# 02_MCU.net
KiCad netlist of a schematic drawn in Altium Designer
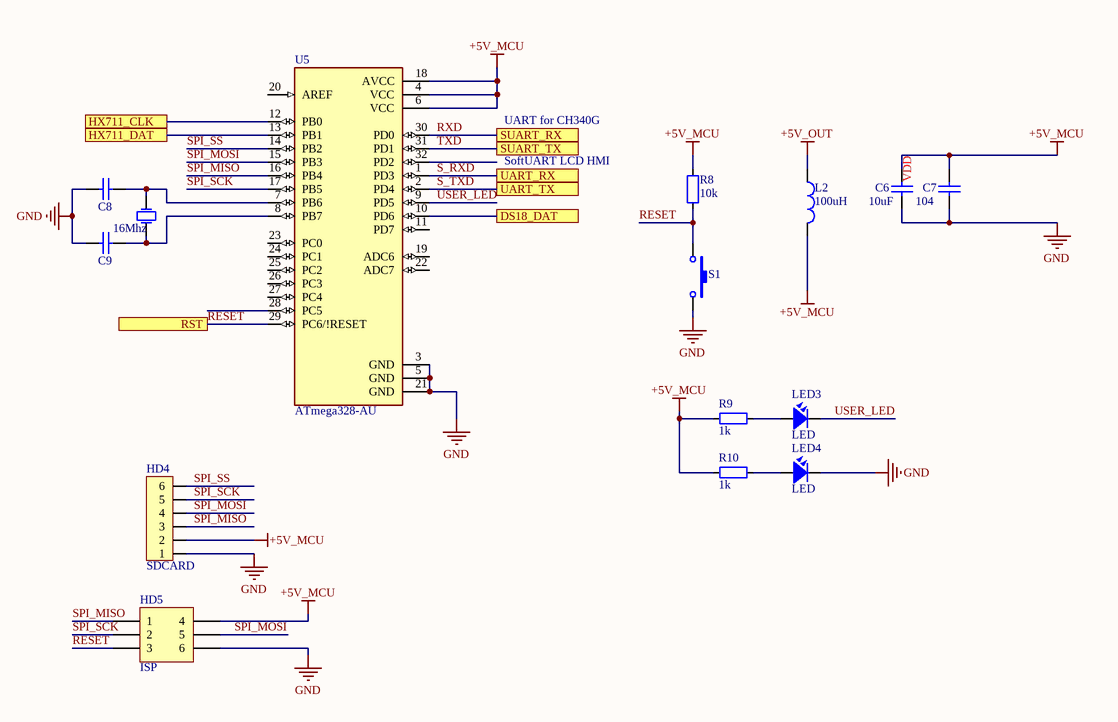
[diagram p0: [02] MCU.SchDoc]

(export (version "E")
  (design (tool "Eeschema 10.0.6"))
  (components
    (comp (ref "C6")
      (value "10uF")
      (footprint "CAP_0805")
      (description "Capacitor")
      (fields (field (name "PUBLISHER") "Altium Limited"))
      (libsource (lib "My Library") (part "CapSMD"))
    )
    (comp (ref "C7")
      (value "104")
      (footprint "CAP_0805")
      (description "Capacitor")
      (fields (field (name "PUBLISHER") "Altium Limited"))
      (libsource (lib "My Library") (part "CapSMD"))
    )
    (comp (ref "C8")
      (value "Capacitor Ceramic")
      (footprint "CAP_0805")
      (description "Capacitor")
      (fields (field (name "PUBLISHER") "Altium Limited"))
      (libsource (lib "My Library") (part "CapSMD"))
    )
    (comp (ref "C9")
      (value "Capacitor Ceramic")
      (footprint "CAP_0805")
      (description "Capacitor")
      (fields (field (name "PUBLISHER") "Altium Limited"))
      (libsource (lib "My Library") (part "CapSMD"))
    )
    (comp (ref "HD4")
      (value "SDCARD")
      (footprint "CON_6P")
      (description "Header IDC, 6 x 1 Pin Vertical 2.54mm Pitch (Non-Boxed, Male)")
      (fields
        (field (name "MANUFACTURER") "Würth Elektronik eiSos GmbH")
        (field (name "PARTNO") "613002143121")
        (field (name "CREATED BY") "Karrer Zheng")
      )
      (libsource (lib "My Library") (part "Header6"))
    )
    (comp (ref "HD5")
      (value "ISP")
      (footprint "HDR2X3_CEN")
      (description "Header, 3-Pin, Dual row")
      (fields (field (name "PUBLISHER") "Altium Limited"))
      (libsource (lib "My Library") (part "Header 3X2A"))
    )
    (comp (ref "L2")
      (value "100uH")
      (footprint "RES-SMD-0805")
      (description "Inductor")
      (libsource (lib "My Library") (part "Inductor"))
    )
    (comp (ref "LED3")
      (value "LED")
      (footprint "LED-0805-Red")
      (description "LED Single colour Green and Red")
      (libsource (lib "My Library") (part "LED"))
    )
    (comp (ref "LED4")
      (value "LED")
      (footprint "LED-0805-Red")
      (description "LED Single colour Green and Red")
      (libsource (lib "My Library") (part "LED"))
    )
    (comp (ref "R8")
      (value "10k")
      (footprint "RES-SMD-0805")
      (description "Resistor")
      (fields
        (field (name "MANUFACTURER") "Generic Components")
        (field (name "PUBLISHER") "Altium Hobart Technology Centre")
      )
      (libsource (lib "My Library") (part "Resistor - SMD"))
    )
    (comp (ref "R9")
      (value "1k")
      (footprint "RES-SMD-0805")
      (description "Resistor")
      (fields
        (field (name "MANUFACTURER") "Generic Components")
        (field (name "PUBLISHER") "Altium Hobart Technology Centre")
      )
      (libsource (lib "My Library") (part "Resistor - SMD"))
    )
    (comp (ref "R10")
      (value "1k")
      (footprint "RES-SMD-0805")
      (description "Resistor")
      (fields
        (field (name "MANUFACTURER") "Generic Components")
        (field (name "PUBLISHER") "Altium Hobart Technology Centre")
      )
      (libsource (lib "My Library") (part "Resistor - SMD"))
    )
    (comp (ref "S1")
      (value "SW-SMD")
      (footprint "SW-SMD")
      (description "Switch")
      (fields (field (name "PUBLISHER") "Altium Limited"))
      (libsource (lib "My Library") (part "SW-SMD"))
    )
    (comp (ref "U5")
      (value "ATmega328-AU")
      (footprint "TQFP 32")
      (fields (field (name "PUBLISHER") "Altium Limited"))
      (libsource (lib "My Library") (part "ATmega328-AU"))
    )
    (comp (ref "Y1")
      (value "16Mhz")
      (footprint "XTAL")
      (description "Crystal Oscillator")
      (fields (field (name "PUBLISHER") "Altium Limited"))
      (libsource (lib "My Library") (part "XTAL"))
    )
  )
  (nets
    (net (code "1") (name "+5V_MCU") (class "Default")
      (node (ref "C6") (pin "2") (pinfunction "2_2") (pintype "passive"))
      (node (ref "C7") (pin "2") (pinfunction "2_2") (pintype "passive"))
      (node (ref "HD4") (pin "2") (pinfunction "2_2") (pintype "passive"))
      (node (ref "HD5") (pin "4") (pinfunction "4_4") (pintype "passive"))
      (node (ref "L2") (pin "2") (pinfunction "2_2") (pintype "passive"))
      (node (ref "R10") (pin "1") (pinfunction "1_1") (pintype "passive"))
      (node (ref "R8") (pin "1") (pinfunction "1_1") (pintype "passive"))
      (node (ref "R9") (pin "1") (pinfunction "1_1") (pintype "passive"))
      (node (ref "U5") (pin "18") (pinfunction "AVCC_18") (pintype "power_in"))
      (node (ref "U5") (pin "4") (pinfunction "VCC_4") (pintype "power_in"))
      (node (ref "U5") (pin "6") (pinfunction "VCC_6") (pintype "power_in"))
    )
    (net (code "2") (name "+5V_OUT") (class "Default")
      (node (ref "L2") (pin "1") (pinfunction "1_1") (pintype "passive"))
    )
    (net (code "3") (name "/DS18_DAT") (class "Default")
      (node (ref "U5") (pin "10") (pinfunction "PD6_10") (pintype "bidirectional"))
    )
    (net (code "4") (name "/HX711_CLK") (class "Default")
      (node (ref "U5") (pin "12") (pinfunction "PB0_12") (pintype "bidirectional"))
    )
    (net (code "5") (name "/HX711_DAT") (class "Default")
      (node (ref "U5") (pin "13") (pinfunction "PB1_13") (pintype "bidirectional"))
    )
    (net (code "6") (name "/RESET") (class "Default")
      (node (ref "HD5") (pin "3") (pinfunction "3_3") (pintype "passive"))
      (node (ref "R8") (pin "2") (pinfunction "2_2") (pintype "passive"))
      (node (ref "S1") (pin "1") (pinfunction "1_1") (pintype "passive"))
      (node (ref "U5") (pin "29") (pinfunction "PC6/!RESET_29") (pintype "bidirectional"))
    )
    (net (code "7") (name "/RXD") (class "Default")
      (node (ref "U5") (pin "30") (pinfunction "PD0_30") (pintype "bidirectional"))
    )
    (net (code "8") (name "/SPI_MISO") (class "Default")
      (node (ref "HD4") (pin "3") (pinfunction "3_3") (pintype "passive"))
      (node (ref "HD5") (pin "1") (pinfunction "1_1") (pintype "passive"))
      (node (ref "U5") (pin "16") (pinfunction "PB4_16") (pintype "bidirectional"))
    )
    (net (code "9") (name "/SPI_MOSI") (class "Default")
      (node (ref "HD4") (pin "4") (pinfunction "4_4") (pintype "passive"))
      (node (ref "HD5") (pin "5") (pinfunction "5_5") (pintype "passive"))
      (node (ref "U5") (pin "15") (pinfunction "PB3_15") (pintype "bidirectional"))
    )
    (net (code "10") (name "/SPI_SCK") (class "Default")
      (node (ref "HD4") (pin "5") (pinfunction "5_5") (pintype "passive"))
      (node (ref "HD5") (pin "2") (pinfunction "2_2") (pintype "passive"))
      (node (ref "U5") (pin "17") (pinfunction "PB5_17") (pintype "bidirectional"))
    )
    (net (code "11") (name "/SPI_SS") (class "Default")
      (node (ref "HD4") (pin "6") (pinfunction "6_6") (pintype "passive"))
      (node (ref "U5") (pin "14") (pinfunction "PB2_14") (pintype "bidirectional"))
    )
    (net (code "12") (name "/S_RXD") (class "Default")
      (node (ref "U5") (pin "1") (pinfunction "PD3_1") (pintype "bidirectional"))
    )
    (net (code "13") (name "/S_TXD") (class "Default")
      (node (ref "U5") (pin "2") (pinfunction "PD4_2") (pintype "bidirectional"))
    )
    (net (code "14") (name "/TXD") (class "Default")
      (node (ref "U5") (pin "31") (pinfunction "PD1_31") (pintype "bidirectional"))
    )
    (net (code "15") (name "/USER_LED") (class "Default")
      (node (ref "LED3") (pin "2") (pinfunction "2_2") (pintype "passive"))
      (node (ref "U5") (pin "9") (pinfunction "PD5_9") (pintype "bidirectional"))
    )
    (net (code "16") (name "GND") (class "Default")
      (node (ref "C6") (pin "1") (pinfunction "1_1") (pintype "passive"))
      (node (ref "C7") (pin "1") (pinfunction "1_1") (pintype "passive"))
      (node (ref "C8") (pin "1") (pinfunction "1_1") (pintype "passive"))
      (node (ref "C9") (pin "1") (pinfunction "1_1") (pintype "passive"))
      (node (ref "HD4") (pin "1") (pinfunction "1_1") (pintype "passive"))
      (node (ref "HD5") (pin "6") (pinfunction "6_6") (pintype "passive"))
      (node (ref "LED4") (pin "2") (pinfunction "2_2") (pintype "passive"))
      (node (ref "S1") (pin "2") (pinfunction "2_2") (pintype "passive"))
      (node (ref "U5") (pin "21") (pinfunction "GND_21") (pintype "power_in"))
      (node (ref "U5") (pin "3") (pinfunction "GND_3") (pintype "power_in"))
      (node (ref "U5") (pin "5") (pinfunction "GND_5") (pintype "power_in"))
    )
    (net (code "17") (name "Net-(LED3-Pad1)") (class "Default")
      (node (ref "LED3") (pin "1") (pinfunction "1_1") (pintype "passive"))
      (node (ref "R9") (pin "2") (pinfunction "2_2") (pintype "passive"))
    )
    (net (code "18") (name "Net-(LED4-Pad1)") (class "Default")
      (node (ref "LED4") (pin "1") (pinfunction "1_1") (pintype "passive"))
      (node (ref "R10") (pin "2") (pinfunction "2_2") (pintype "passive"))
    )
    (net (code "19") (name "Net-(U5-PB6)") (class "Default")
      (node (ref "C8") (pin "2") (pinfunction "2_2") (pintype "passive"))
      (node (ref "U5") (pin "7") (pinfunction "PB6_7") (pintype "bidirectional"))
      (node (ref "Y1") (pin "2") (pinfunction "OSC2_2") (pintype "passive"))
    )
    (net (code "20") (name "Net-(U5-PB7)") (class "Default")
      (node (ref "C9") (pin "2") (pinfunction "2_2") (pintype "passive"))
      (node (ref "U5") (pin "8") (pinfunction "PB7_8") (pintype "bidirectional"))
      (node (ref "Y1") (pin "1") (pinfunction "OSC1_1") (pintype "passive"))
    )
    (net (code "21") (name "unconnected-(U5-ADC6-Pad19)") (class "Default")
      (node (ref "U5") (pin "19") (pinfunction "ADC6_19") (pintype "bidirectional"))
    )
    (net (code "22") (name "unconnected-(U5-ADC7-Pad22)") (class "Default")
      (node (ref "U5") (pin "22") (pinfunction "ADC7_22") (pintype "bidirectional"))
    )
    (net (code "23") (name "unconnected-(U5-AREF-Pad20)") (class "Default")
      (node (ref "U5") (pin "20") (pinfunction "AREF_20") (pintype "input"))
    )
    (net (code "24") (name "unconnected-(U5-PC0-Pad23)") (class "Default")
      (node (ref "U5") (pin "23") (pinfunction "PC0_23") (pintype "bidirectional"))
    )
    (net (code "25") (name "unconnected-(U5-PC1-Pad24)") (class "Default")
      (node (ref "U5") (pin "24") (pinfunction "PC1_24") (pintype "bidirectional"))
    )
    (net (code "26") (name "unconnected-(U5-PC2-Pad25)") (class "Default")
      (node (ref "U5") (pin "25") (pinfunction "PC2_25") (pintype "bidirectional"))
    )
    (net (code "27") (name "unconnected-(U5-PC3-Pad26)") (class "Default")
      (node (ref "U5") (pin "26") (pinfunction "PC3_26") (pintype "bidirectional"))
    )
    (net (code "28") (name "unconnected-(U5-PC4-Pad27)") (class "Default")
      (node (ref "U5") (pin "27") (pinfunction "PC4_27") (pintype "bidirectional"))
    )
    (net (code "29") (name "unconnected-(U5-PC5-Pad28)") (class "Default")
      (node (ref "U5") (pin "28") (pinfunction "PC5_28") (pintype "bidirectional"))
    )
    (net (code "30") (name "unconnected-(U5-PD2-Pad32)") (class "Default")
      (node (ref "U5") (pin "32") (pinfunction "PD2_32") (pintype "bidirectional"))
    )
    (net (code "31") (name "unconnected-(U5-PD7-Pad11)") (class "Default")
      (node (ref "U5") (pin "11") (pinfunction "PD7_11") (pintype "bidirectional"))
    )
  )
)
